# rca_studio_II_mutli.net
KiCad netlist of a schematic drawn in EAGLE
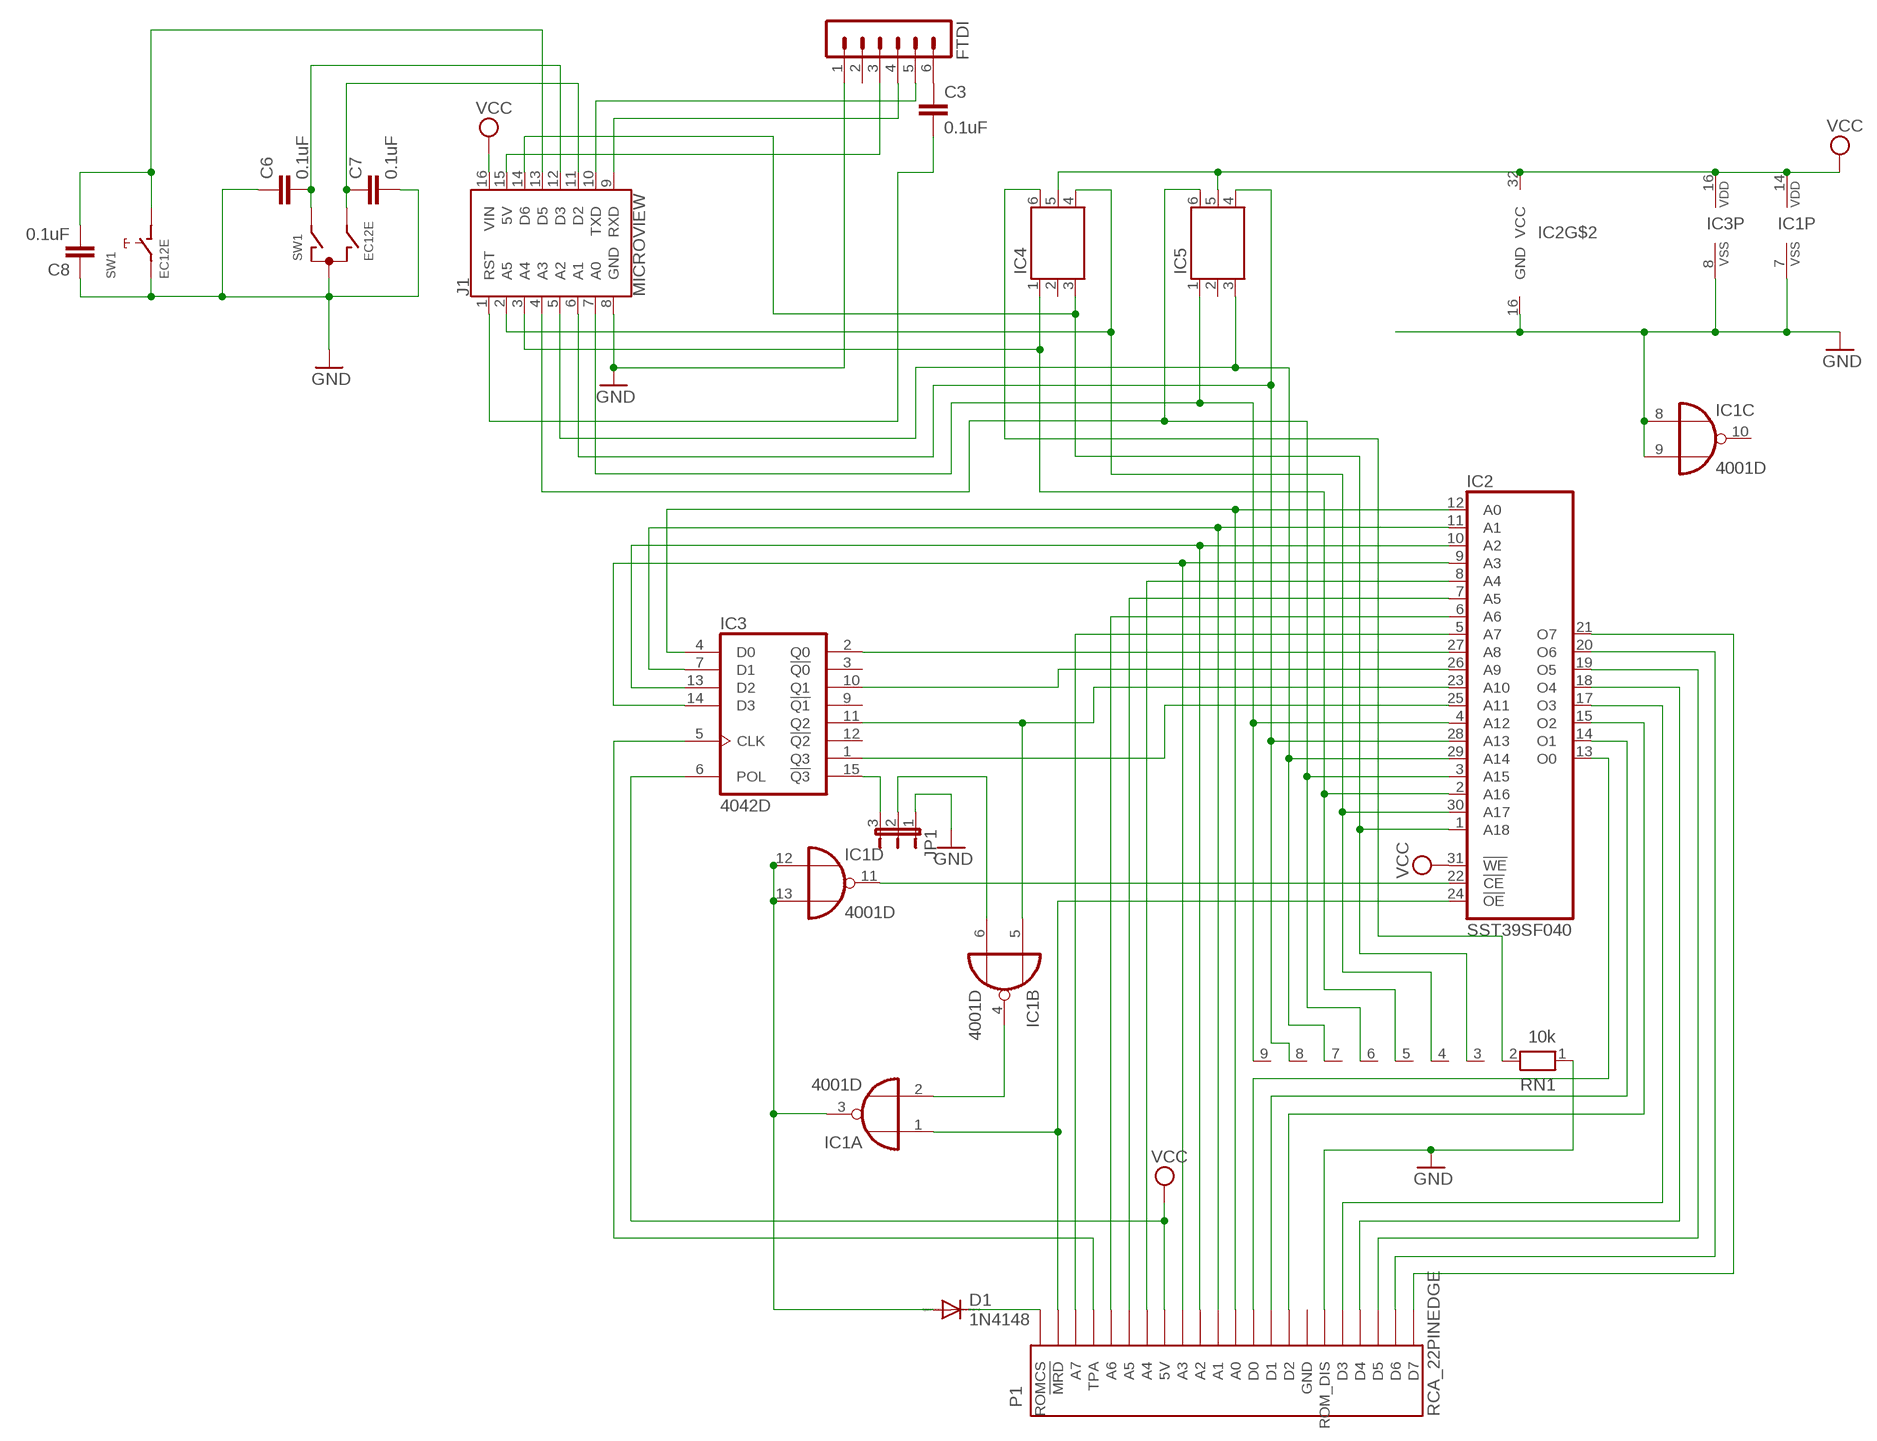
[diagram p0: schematic, sheet 1]

(export (version "E")
  (design (tool "Eeschema 10.0.6"))
  (components
    (comp (ref "C3")
      (value "0.1uF")
      (footprint "eagle-import:C0805")
      (libsource (lib "eagle-import") (part "C-EUC0805"))
    )
    (comp (ref "C6")
      (value "0.1uF")
      (footprint "eagle-import:C0805")
      (libsource (lib "eagle-import") (part "C-EUC0805"))
    )
    (comp (ref "C7")
      (value "0.1uF")
      (footprint "eagle-import:C0805")
      (libsource (lib "eagle-import") (part "C-EUC0805"))
    )
    (comp (ref "C8")
      (value "0.1uF")
      (footprint "eagle-import:C0805")
      (libsource (lib "eagle-import") (part "C-EUC0805"))
    )
    (comp (ref "D1")
      (value "1N4148")
      (footprint "eagle-import:DO35-7")
      (libsource (lib "eagle-import") (part "1N4148DO35-7"))
    )
    (comp (ref "FTDI")
      (value "MA06-1")
      (footprint "eagle-import:MA06-1")
      (libsource (lib "eagle-import") (part "MA06-1"))
    )
    (comp (ref "IC1")
      (value "4001D")
      (footprint "eagle-import:SO14")
      (libsource (lib "eagle-import") (part "4001D"))
    )
    (comp (ref "IC2")
      (value "SST39SF040")
      (footprint "eagle-import:S32")
      (libsource (lib "eagle-import") (part "SST39SF040"))
    )
    (comp (ref "IC3")
      (value "4042D")
      (footprint "eagle-import:SO16")
      (libsource (lib "eagle-import") (part "4042D"))
    )
    (comp (ref "IC4")
      (value "HEXENCODERHEXENCODER")
      (footprint "eagle-import:HEXENCODER")
      (libsource (lib "eagle-import") (part "HEXENCODERHEXENCODER"))
    )
    (comp (ref "IC5")
      (value "HEXENCODERHEXENCODER")
      (footprint "eagle-import:HEXENCODER")
      (libsource (lib "eagle-import") (part "HEXENCODERHEXENCODER"))
    )
    (comp (ref "J1")
      (value "MICROVIEW")
      (footprint "eagle-import:MV-DIP16-NODIMENSION")
      (libsource (lib "eagle-import") (part "MICROVIEW-16ND"))
    )
    (comp (ref "JP1")
      (value "JP2E")
      (footprint "eagle-import:JP2")
      (libsource (lib "eagle-import") (part "JP2E"))
    )
    (comp (ref "P1")
      (value "RCA_22PINEDGE")
      (footprint "eagle-import:RCA_22PINEDGE")
      (libsource (lib "eagle-import") (part "RCA_22PINEDGE"))
    )
    (comp (ref "RN1")
      (value "10k")
      (footprint "eagle-import:RN-9")
      (libsource (lib "eagle-import") (part "RN08"))
    )
    (comp (ref "SW1")
      (value "EC12E")
      (footprint "eagle-import:ALPS_EC12E_SW")
      (fields (field (name "MPN") "EC12E2424407"))
      (libsource (lib "eagle-import") (part "EC12E_SW"))
    )
  )
  (nets
    (net (code "1") (name "GND") (class "Default")
      (node (ref "C6") (pin "1") (pinfunction "1_1") (pintype "passive"))
      (node (ref "C7") (pin "2") (pinfunction "2_2") (pintype "passive"))
      (node (ref "C8") (pin "1") (pinfunction "1_1") (pintype "passive"))
      (node (ref "FTDI") (pin "1") (pinfunction "1_1") (pintype "passive"))
      (node (ref "IC1") (pin "7") (pinfunction "VSS_7") (pintype "power_in"))
      (node (ref "IC1") (pin "8") (pinfunction "I0_8") (pintype "input"))
      (node (ref "IC1") (pin "9") (pinfunction "I1_9") (pintype "input"))
      (node (ref "IC2") (pin "16") (pinfunction "GND_16") (pintype "power_in"))
      (node (ref "IC3") (pin "8") (pinfunction "VSS_8") (pintype "power_in"))
      (node (ref "J1") (pin "8") (pinfunction "GND_8") (pintype "power_in"))
      (node (ref "JP1") (pin "1") (pinfunction "1_1") (pintype "passive"))
      (node (ref "P1") (pin "6") (pinfunction "ROM_DIS_6") (pintype "passive"))
      (node (ref "RN1") (pin "1") (pinfunction "1_1") (pintype "passive"))
      (node (ref "SW1") (pin "C") (pinfunction "C_C") (pintype "passive"))
      (node (ref "SW1") (pin "E") (pinfunction "2_E") (pintype "passive"))
    )
    (net (code "2") (name "Net-(C3-Pad1)") (class "Default")
      (node (ref "C3") (pin "1") (pinfunction "1_1") (pintype "passive"))
      (node (ref "FTDI") (pin "6") (pinfunction "6_6") (pintype "passive"))
    )
    (net (code "3") (name "Net-(IC1A-I0)") (class "Default")
      (node (ref "IC1") (pin "1") (pinfunction "I0_1") (pintype "input"))
      (node (ref "IC2") (pin "24") (pinfunction "~{OE}_24") (pintype "input"))
      (node (ref "P1") (pin "21") (pinfunction "~{MRD}_21") (pintype "passive"))
    )
    (net (code "4") (name "Net-(IC1A-I1)") (class "Default")
      (node (ref "IC1") (pin "2") (pinfunction "I1_2") (pintype "input"))
      (node (ref "IC1") (pin "4") (pinfunction "O_4") (pintype "output"))
    )
    (net (code "5") (name "Net-(IC1A-O)") (class "Default")
      (node (ref "D1") (pin "A") (pinfunction "A_A") (pintype "passive"))
      (node (ref "IC1") (pin "12") (pinfunction "I0_12") (pintype "input"))
      (node (ref "IC1") (pin "13") (pinfunction "I1_13") (pintype "input"))
      (node (ref "IC1") (pin "3") (pinfunction "O_3") (pintype "output"))
    )
    (net (code "6") (name "Net-(IC1B-I0)") (class "Default")
      (node (ref "IC1") (pin "5") (pinfunction "I0_5") (pintype "input"))
      (node (ref "IC2") (pin "23") (pinfunction "A10_23") (pintype "input"))
      (node (ref "IC3") (pin "11") (pinfunction "Q2_11") (pintype "output"))
    )
    (net (code "7") (name "Net-(IC1B-I1)") (class "Default")
      (node (ref "IC1") (pin "6") (pinfunction "I1_6") (pintype "input"))
      (node (ref "JP1") (pin "2") (pinfunction "2_2") (pintype "passive"))
    )
    (net (code "8") (name "Net-(IC1D-O)") (class "Default")
      (node (ref "IC1") (pin "11") (pinfunction "O_11") (pintype "output"))
      (node (ref "IC2") (pin "22") (pinfunction "~{CE}_22") (pintype "input"))
    )
    (net (code "9") (name "Net-(IC2A-A0)") (class "Default")
      (node (ref "IC2") (pin "12") (pinfunction "A0_12") (pintype "input"))
      (node (ref "IC3") (pin "4") (pinfunction "D0_4") (pintype "input"))
      (node (ref "P1") (pin "11") (pinfunction "A0_11") (pintype "passive"))
    )
    (net (code "10") (name "Net-(IC2A-A1)") (class "Default")
      (node (ref "IC2") (pin "11") (pinfunction "A1_11") (pintype "input"))
      (node (ref "IC3") (pin "7") (pinfunction "D1_7") (pintype "input"))
      (node (ref "P1") (pin "12") (pinfunction "A1_12") (pintype "passive"))
    )
    (net (code "11") (name "Net-(IC2A-A2)") (class "Default")
      (node (ref "IC2") (pin "10") (pinfunction "A2_10") (pintype "input"))
      (node (ref "IC3") (pin "13") (pinfunction "D2_13") (pintype "input"))
      (node (ref "P1") (pin "13") (pinfunction "A2_13") (pintype "passive"))
    )
    (net (code "12") (name "Net-(IC2A-A3)") (class "Default")
      (node (ref "IC2") (pin "9") (pinfunction "A3_9") (pintype "input"))
      (node (ref "IC3") (pin "14") (pinfunction "D3_14") (pintype "input"))
      (node (ref "P1") (pin "14") (pinfunction "A3_14") (pintype "passive"))
    )
    (net (code "13") (name "Net-(IC2A-A4)") (class "Default")
      (node (ref "IC2") (pin "8") (pinfunction "A4_8") (pintype "input"))
      (node (ref "P1") (pin "16") (pinfunction "A4_16") (pintype "passive"))
    )
    (net (code "14") (name "Net-(IC2A-A5)") (class "Default")
      (node (ref "IC2") (pin "7") (pinfunction "A5_7") (pintype "input"))
      (node (ref "P1") (pin "17") (pinfunction "A5_17") (pintype "passive"))
    )
    (net (code "15") (name "Net-(IC2A-A6)") (class "Default")
      (node (ref "IC2") (pin "6") (pinfunction "A6_6") (pintype "input"))
      (node (ref "P1") (pin "18") (pinfunction "A6_18") (pintype "passive"))
    )
    (net (code "16") (name "Net-(IC2A-A7)") (class "Default")
      (node (ref "IC2") (pin "5") (pinfunction "A7_5") (pintype "input"))
      (node (ref "P1") (pin "20") (pinfunction "A7_20") (pintype "passive"))
    )
    (net (code "17") (name "Net-(IC2A-A8)") (class "Default")
      (node (ref "IC2") (pin "27") (pinfunction "A8_27") (pintype "input"))
      (node (ref "IC3") (pin "2") (pinfunction "Q0_2") (pintype "output"))
    )
    (net (code "18") (name "Net-(IC2A-A9)") (class "Default")
      (node (ref "IC2") (pin "26") (pinfunction "A9_26") (pintype "input"))
      (node (ref "IC3") (pin "10") (pinfunction "Q1_10") (pintype "output"))
    )
    (net (code "19") (name "Net-(IC2A-A11)") (class "Default")
      (node (ref "IC2") (pin "25") (pinfunction "A11_25") (pintype "input"))
      (node (ref "IC3") (pin "1") (pinfunction "Q3_1") (pintype "output"))
    )
    (net (code "20") (name "Net-(IC2A-A12)") (class "Default")
      (node (ref "IC2") (pin "4") (pinfunction "A12_4") (pintype "input"))
      (node (ref "IC5") (pin "1") (pinfunction "1_1") (pintype "passive"))
      (node (ref "J1") (pin "7") (pinfunction "A0_7") (pintype "output"))
      (node (ref "RN1") (pin "9") (pinfunction "9_9") (pintype "passive"))
    )
    (net (code "21") (name "Net-(IC2A-A13)") (class "Default")
      (node (ref "IC2") (pin "28") (pinfunction "A13_28") (pintype "input"))
      (node (ref "IC5") (pin "4") (pinfunction "2_4") (pintype "passive"))
      (node (ref "J1") (pin "6") (pinfunction "A1_6") (pintype "output"))
      (node (ref "RN1") (pin "8") (pinfunction "8_8") (pintype "passive"))
    )
    (net (code "22") (name "Net-(IC2A-A14)") (class "Default")
      (node (ref "IC2") (pin "29") (pinfunction "A14_29") (pintype "input"))
      (node (ref "IC5") (pin "3") (pinfunction "4_3") (pintype "passive"))
      (node (ref "J1") (pin "5") (pinfunction "A2_5") (pintype "output"))
      (node (ref "RN1") (pin "7") (pinfunction "7_7") (pintype "passive"))
    )
    (net (code "23") (name "Net-(IC2A-A15)") (class "Default")
      (node (ref "IC2") (pin "3") (pinfunction "A15_3") (pintype "input"))
      (node (ref "IC5") (pin "6") (pinfunction "8_6") (pintype "passive"))
      (node (ref "J1") (pin "4") (pinfunction "A3_4") (pintype "output"))
      (node (ref "RN1") (pin "6") (pinfunction "6_6") (pintype "passive"))
    )
    (net (code "24") (name "Net-(IC2A-A16)") (class "Default")
      (node (ref "IC2") (pin "2") (pinfunction "A16_2") (pintype "input"))
      (node (ref "IC4") (pin "1") (pinfunction "1_1") (pintype "passive"))
      (node (ref "J1") (pin "3") (pinfunction "A4_3") (pintype "output"))
      (node (ref "RN1") (pin "5") (pinfunction "5_5") (pintype "passive"))
    )
    (net (code "25") (name "Net-(IC2A-A17)") (class "Default")
      (node (ref "IC2") (pin "30") (pinfunction "A17_30") (pintype "input"))
      (node (ref "IC4") (pin "4") (pinfunction "2_4") (pintype "passive"))
      (node (ref "J1") (pin "2") (pinfunction "A5_2") (pintype "output"))
      (node (ref "RN1") (pin "4") (pinfunction "4_4") (pintype "passive"))
    )
    (net (code "26") (name "Net-(IC2A-A18)") (class "Default")
      (node (ref "IC2") (pin "1") (pinfunction "A18_1") (pintype "input"))
      (node (ref "IC4") (pin "3") (pinfunction "4_3") (pintype "passive"))
      (node (ref "J1") (pin "14") (pinfunction "D6_14") (pintype "output"))
      (node (ref "RN1") (pin "3") (pinfunction "3_3") (pintype "passive"))
    )
    (net (code "27") (name "Net-(IC2A-O0)") (class "Default")
      (node (ref "IC2") (pin "13") (pinfunction "O0_13") (pintype "tri_state"))
      (node (ref "P1") (pin "10") (pinfunction "D0_10") (pintype "passive"))
    )
    (net (code "28") (name "Net-(IC2A-O1)") (class "Default")
      (node (ref "IC2") (pin "14") (pinfunction "O1_14") (pintype "tri_state"))
      (node (ref "P1") (pin "9") (pinfunction "D1_9") (pintype "passive"))
    )
    (net (code "29") (name "Net-(IC2A-O2)") (class "Default")
      (node (ref "IC2") (pin "15") (pinfunction "O2_15") (pintype "tri_state"))
      (node (ref "P1") (pin "8") (pinfunction "D2_8") (pintype "passive"))
    )
    (net (code "30") (name "Net-(IC2A-O3)") (class "Default")
      (node (ref "IC2") (pin "17") (pinfunction "O3_17") (pintype "tri_state"))
      (node (ref "P1") (pin "5") (pinfunction "D3_5") (pintype "passive"))
    )
    (net (code "31") (name "Net-(IC2A-O4)") (class "Default")
      (node (ref "IC2") (pin "18") (pinfunction "O4_18") (pintype "tri_state"))
      (node (ref "P1") (pin "4") (pinfunction "D4_4") (pintype "passive"))
    )
    (net (code "32") (name "Net-(IC2A-O5)") (class "Default")
      (node (ref "IC2") (pin "19") (pinfunction "O5_19") (pintype "tri_state"))
      (node (ref "P1") (pin "3") (pinfunction "D5_3") (pintype "passive"))
    )
    (net (code "33") (name "Net-(IC2A-O6)") (class "Default")
      (node (ref "IC2") (pin "20") (pinfunction "O6_20") (pintype "tri_state"))
      (node (ref "P1") (pin "2") (pinfunction "D6_2") (pintype "passive"))
    )
    (net (code "34") (name "Net-(IC2A-O7)") (class "Default")
      (node (ref "IC2") (pin "21") (pinfunction "O7_21") (pintype "tri_state"))
      (node (ref "P1") (pin "1") (pinfunction "D7_1") (pintype "passive"))
    )
    (net (code "35") (name "Net-(IC3A-CLK)") (class "Default")
      (node (ref "IC3") (pin "5") (pinfunction "CLK_5") (pintype "input"))
      (node (ref "P1") (pin "19") (pinfunction "TPA_19") (pintype "passive"))
    )
    (net (code "36") (name "Net-(IC3A-~{Q3})") (class "Default")
      (node (ref "IC3") (pin "15") (pinfunction "~{Q3}_15") (pintype "output"))
      (node (ref "JP1") (pin "3") (pinfunction "3_3") (pintype "passive"))
    )
    (net (code "37") (name "Net-(IC4-8)") (class "Default")
      (node (ref "IC4") (pin "6") (pinfunction "8_6") (pintype "passive"))
      (node (ref "RN1") (pin "2") (pinfunction "2_2") (pintype "passive"))
    )
    (net (code "38") (name "Net-(J1-5V)") (class "Default")
      (node (ref "FTDI") (pin "3") (pinfunction "3_3") (pintype "passive"))
      (node (ref "J1") (pin "15") (pinfunction "5V_15") (pintype "output"))
    )
    (net (code "39") (name "Net-(J1-D2)") (class "Default")
      (node (ref "C7") (pin "1") (pinfunction "1_1") (pintype "passive"))
      (node (ref "J1") (pin "11") (pinfunction "D2_11") (pintype "output"))
      (node (ref "SW1") (pin "B") (pinfunction "B_B") (pintype "passive"))
    )
    (net (code "40") (name "Net-(J1-D3)") (class "Default")
      (node (ref "C6") (pin "2") (pinfunction "2_2") (pintype "passive"))
      (node (ref "J1") (pin "12") (pinfunction "D3_12") (pintype "output"))
      (node (ref "SW1") (pin "A") (pinfunction "A_A") (pintype "passive"))
    )
    (net (code "41") (name "Net-(J1-D5)") (class "Default")
      (node (ref "C8") (pin "2") (pinfunction "2_2") (pintype "passive"))
      (node (ref "J1") (pin "13") (pinfunction "D5_13") (pintype "output"))
      (node (ref "SW1") (pin "D") (pinfunction "1_D") (pintype "passive"))
    )
    (net (code "42") (name "Net-(J1-RST)") (class "Default")
      (node (ref "C3") (pin "2") (pinfunction "2_2") (pintype "passive"))
      (node (ref "J1") (pin "1") (pinfunction "RST_1") (pintype "output"))
    )
    (net (code "43") (name "Net-(J1-RXD)") (class "Default")
      (node (ref "FTDI") (pin "4") (pinfunction "4_4") (pintype "passive"))
      (node (ref "J1") (pin "9") (pinfunction "RXD_9") (pintype "output"))
    )
    (net (code "44") (name "Net-(J1-TXD)") (class "Default")
      (node (ref "FTDI") (pin "5") (pinfunction "5_5") (pintype "passive"))
      (node (ref "J1") (pin "10") (pinfunction "TXD_10") (pintype "output"))
    )
    (net (code "45") (name "Net-(P1-ROMCS)") (class "Default")
      (node (ref "D1") (pin "C") (pinfunction "C_C") (pintype "passive"))
      (node (ref "P1") (pin "22") (pinfunction "ROMCS_22") (pintype "passive"))
    )
    (net (code "46") (name "VCC") (class "Default")
      (node (ref "IC1") (pin "14") (pinfunction "VDD_14") (pintype "power_in"))
      (node (ref "IC2") (pin "31") (pinfunction "~{WE}_31") (pintype "input"))
      (node (ref "IC2") (pin "32") (pinfunction "VCC_32") (pintype "power_in"))
      (node (ref "IC3") (pin "16") (pinfunction "VDD_16") (pintype "power_in"))
      (node (ref "IC3") (pin "6") (pinfunction "POL_6") (pintype "input"))
      (node (ref "IC4") (pin "5") (pinfunction "C2_5") (pintype "passive"))
      (node (ref "IC5") (pin "5") (pinfunction "C2_5") (pintype "passive"))
      (node (ref "J1") (pin "16") (pinfunction "VIN_16") (pintype "passive"))
      (node (ref "P1") (pin "15") (pinfunction "5V_15") (pintype "passive"))
    )
    (net (code "47") (name "unconnected-(FTDI-Pad2)") (class "Default")
      (node (ref "FTDI") (pin "2") (pinfunction "2_2") (pintype "passive"))
    )
    (net (code "48") (name "unconnected-(IC1C-O-Pad10)") (class "Default")
      (node (ref "IC1") (pin "10") (pinfunction "O_10") (pintype "output"))
    )
    (net (code "49") (name "unconnected-(IC3A-~{Q0}-Pad3)") (class "Default")
      (node (ref "IC3") (pin "3") (pinfunction "~{Q0}_3") (pintype "output"))
    )
    (net (code "50") (name "unconnected-(IC3A-~{Q1}-Pad9)") (class "Default")
      (node (ref "IC3") (pin "9") (pinfunction "~{Q1}_9") (pintype "output"))
    )
    (net (code "51") (name "unconnected-(IC3A-~{Q2}-Pad12)") (class "Default")
      (node (ref "IC3") (pin "12") (pinfunction "~{Q2}_12") (pintype "output"))
    )
    (net (code "52") (name "unconnected-(IC4-C1-Pad2)") (class "Default")
      (node (ref "IC4") (pin "2") (pinfunction "C1_2") (pintype "passive"))
    )
    (net (code "53") (name "unconnected-(IC5-C1-Pad2)") (class "Default")
      (node (ref "IC5") (pin "2") (pinfunction "C1_2") (pintype "passive"))
    )
    (net (code "54") (name "unconnected-(P1-GND-Pad7)") (class "Default")
      (node (ref "P1") (pin "7") (pinfunction "GND_7") (pintype "passive"))
    )
  )
)
